# HV_Measurements.net
KiCad netlist of a schematic drawn in Altium Designer
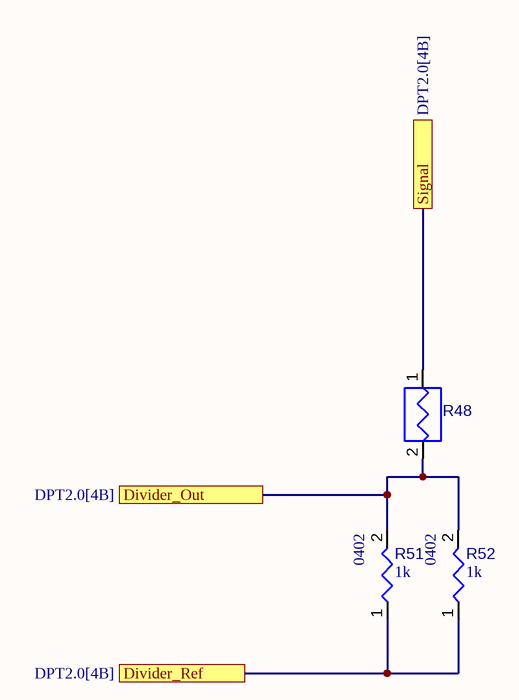
[diagram p0: HV_Measurements.SchDoc]

(export (version "E")
  (design (tool "Eeschema 10.0.6"))
  (components
    (comp (ref "R48")
      (value "RES-2512-SIDE")
      (footprint "RES_2512_SIDE")
      (description "SMD Resistor - 2512 (6432) On It's Side")
      (libsource (lib "2256-GaN Power") (part "RES-SIDE-2"))
    )
    (comp (ref "R51")
      (value "1k")
      (footprint "RES_0402_HIGH")
      (description "SMD Resistor - 0402 (1005 Metric)")
      (fields (field (name "Comment") "RES-0402"))
      (libsource (lib "2256-GaN Power") (part "RES-2"))
    )
    (comp (ref "R52")
      (value "1k")
      (footprint "RES_0402_HIGH")
      (description "SMD Resistor - 0402 (1005 Metric)")
      (fields (field (name "Comment") "RES-0402"))
      (libsource (lib "2256-GaN Power") (part "RES-2"))
    )
  )
  (nets
    (net (code "1") (name "/Divider_Out") (class "Default")
      (node (ref "R48") (pin "2") (pinfunction "2_2") (pintype "passive"))
      (node (ref "R51") (pin "2") (pinfunction "2_2") (pintype "passive"))
      (node (ref "R52") (pin "2") (pinfunction "2_2") (pintype "passive"))
    )
    (net (code "2") (name "/Divider_Ref") (class "Default")
      (node (ref "R51") (pin "1") (pinfunction "1_1") (pintype "passive"))
      (node (ref "R52") (pin "1") (pinfunction "1_1") (pintype "passive"))
    )
    (net (code "3") (name "/Signal") (class "Default")
      (node (ref "R48") (pin "1") (pinfunction "1_1") (pintype "passive"))
    )
  )
)
